# OpAmp_CH1.net
KiCad netlist of a schematic drawn in Altium Designer
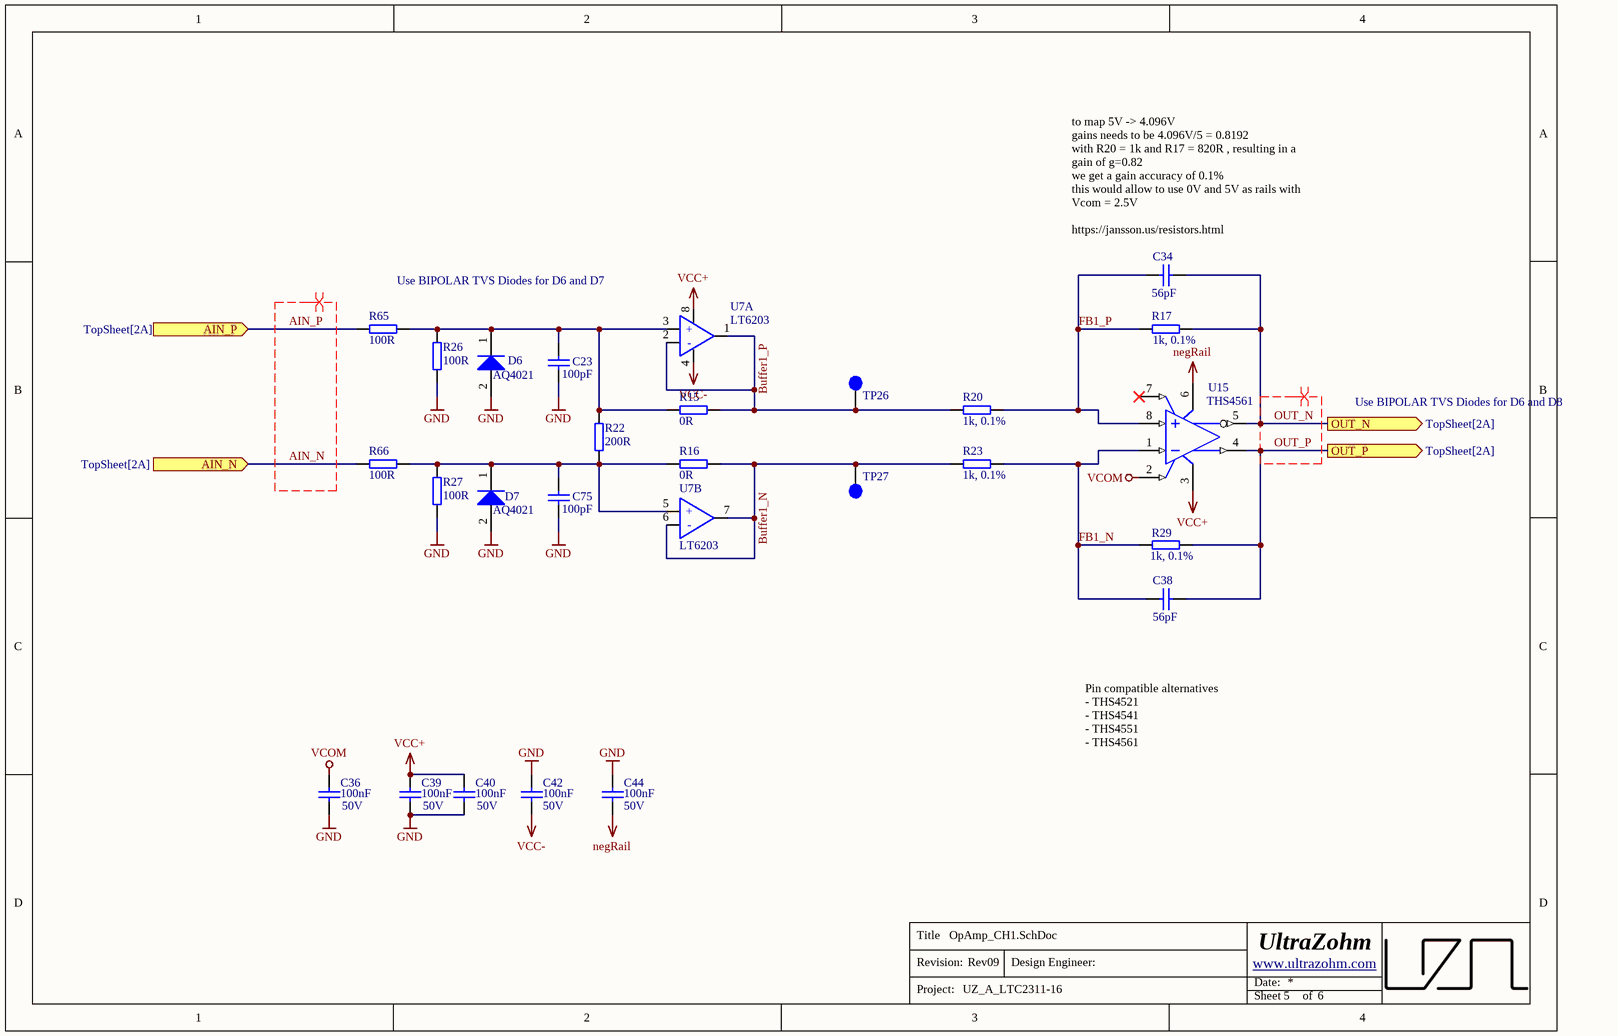
[diagram p0: OpAmp_CH1.SchDoc]

(export (version "E")
  (design (tool "Eeschema 10.0.6"))
  (components
    (comp (ref "C23")
      (value "100pF")
      (footprint "CAPC1608X07N")
      (fields
        (field (name "MF") "Würth Elektronik")
        (field (name "MPN") "885012006057")
        (field (name "VOLTAGE") "50V")
      )
      (libsource (lib "UltraZohm_ADC") (part "Cap_0603"))
    )
    (comp (ref "C34")
      (value "56pF")
      (footprint "CAPC1608X07N")
      (fields
        (field (name "MF") "Kemet")
        (field (name "MPN") "C0603C560J5GACTU")
        (field (name "VOLTAGE") "50V")
      )
      (libsource (lib "UltraZohm_ADC") (part "Cap_0603"))
    )
    (comp (ref "C36")
      (value "100nF")
      (footprint "CAPC1608X07N")
      (fields
        (field (name "MF") "Yageo")
        (field (name "MPN") "CC0603KRX7R9BB104")
        (field (name "VOLTAGE") "50V")
      )
      (libsource (lib "UltraZohm_ADC") (part "Cap_0603"))
    )
    (comp (ref "C38")
      (value "56pF")
      (footprint "CAPC1608X07N")
      (fields
        (field (name "MF") "Kemet")
        (field (name "MPN") "C0603C560J5GACTU")
        (field (name "VOLTAGE") "50V")
      )
      (libsource (lib "UltraZohm_ADC") (part "Cap_0603"))
    )
    (comp (ref "C39")
      (value "100nF")
      (footprint "CAPC1608X07N")
      (fields
        (field (name "MF") "Yageo")
        (field (name "MPN") "CC0603KRX7R9BB104")
        (field (name "VOLTAGE") "50V")
      )
      (libsource (lib "UltraZohm_ADC") (part "Cap_0603"))
    )
    (comp (ref "C40")
      (value "100nF")
      (footprint "CAPC1608X07N")
      (fields
        (field (name "MF") "Yageo")
        (field (name "MPN") "CC0603KRX7R9BB104")
        (field (name "VOLTAGE") "50V")
      )
      (libsource (lib "UltraZohm_ADC") (part "Cap_0603"))
    )
    (comp (ref "C42")
      (value "100nF")
      (footprint "CAPC1608X07N")
      (fields
        (field (name "MF") "Yageo")
        (field (name "MPN") "CC0603KRX7R9BB104")
        (field (name "VOLTAGE") "50V")
      )
      (libsource (lib "UltraZohm_ADC") (part "Cap_0603"))
    )
    (comp (ref "C44")
      (value "100nF")
      (footprint "CAPC1608X07N")
      (fields
        (field (name "MF") "Yageo")
        (field (name "MPN") "CC0603KRX7R9BB104")
        (field (name "VOLTAGE") "50V")
      )
      (libsource (lib "UltraZohm_ADC") (part "Cap_0603"))
    )
    (comp (ref "C75")
      (value "100pF")
      (footprint "CAPC1608X07N")
      (fields
        (field (name "MF") "Würth Elektronik")
        (field (name "MPN") "885012006057")
        (field (name "VOLTAGE") "50V")
      )
      (libsource (lib "UltraZohm_ADC") (part "Cap_0603"))
    )
    (comp (ref "D6")
      (value "AQ4021")
      (footprint "SOD-323_SuppressorDiode")
      (description "ESD Suppressor Diode TVS Bi-Dir 5V")
      (fields (field (name "MF") "Littelfuse") (field (name "MPN") "AQ4021-01FTG-C"))
      (libsource (lib "UltraZohm_ADC") (part "GBLCxx"))
    )
    (comp (ref "D7")
      (value "AQ4021")
      (footprint "SOD-323_SuppressorDiode")
      (description "ESD Suppressor Diode TVS Bi-Dir 5V")
      (fields (field (name "MF") "Littelfuse") (field (name "MPN") "AQ4021-01FTG-C"))
      (libsource (lib "UltraZohm_ADC") (part "GBLCxx"))
    )
    (comp (ref "R15")
      (value "0R")
      (footprint "RESC1608X06N")
      (fields (field (name "MF") "Vishay / Dale") (field (name "MPN") "CRCW06030000Z0EBC"))
      (libsource (lib "UltraZohm_ADC") (part "R_0603"))
    )
    (comp (ref "R16")
      (value "0R")
      (footprint "RESC1608X06N")
      (fields (field (name "MF") "Vishay / Dale") (field (name "MPN") "CRCW06030000Z0EBC"))
      (libsource (lib "UltraZohm_ADC") (part "R_0603"))
    )
    (comp (ref "R17")
      (value "1k, 0.1%")
      (footprint "RESC1608X06N")
      (description "Precision Resistor 1k 0.1% 0603")
      (fields (field (name "MF") "IRC/TT Electronics") (field (name "MPN") "PCF-W0603LF-03-1001-B-P-LT"))
      (libsource (lib "UltraZohm_ADC") (part "R_0603"))
    )
    (comp (ref "R20")
      (value "1k, 0.1%")
      (footprint "RESC1608X06N")
      (description "Precision Resistor 1k 0.1% 0603")
      (fields (field (name "MF") "IRC/TT Electronics") (field (name "MPN") "PCF-W0603LF-03-1001-B-P-LT"))
      (libsource (lib "UltraZohm_ADC") (part "R_0603"))
    )
    (comp (ref "R22")
      (value "200R")
      (footprint "RESC3216X65N")
      (description "WID SMD 1M 5% 0,25W")
      (fields
        (field (name "TOLERANCE") "5%")
        (field (name "MF") "AECOL/Ohmite")
        (field (name "CREATED") "2018_07_20_AGeiger")
      )
      (libsource (lib "UltraZOhm_CarrierBoard") (part "R_1206"))
    )
    (comp (ref "R23")
      (value "1k, 0.1%")
      (footprint "RESC1608X06N")
      (description "Precision Resistor 1k 0.1% 0603")
      (fields (field (name "MF") "IRC/TT Electronics") (field (name "MPN") "PCF-W0603LF-03-1001-B-P-LT"))
      (libsource (lib "UltraZohm_ADC") (part "R_0603"))
    )
    (comp (ref "R26")
      (value "100R")
      (footprint "RESC1608X06N")
      (fields
        (field (name "MF") "Yageo")
        (field (name "MPN") "AC0603FR-13100RL")
        (field (name "TOLERANCE") "1%")
      )
      (libsource (lib "UltraZohm_ADC") (part "R_0603"))
    )
    (comp (ref "R27")
      (value "100R")
      (footprint "RESC1608X06N")
      (fields
        (field (name "MF") "Yageo")
        (field (name "MPN") "AC0603FR-13100RL")
        (field (name "TOLERANCE") "1%")
      )
      (libsource (lib "UltraZohm_ADC") (part "R_0603"))
    )
    (comp (ref "R29")
      (value "1k, 0.1%")
      (footprint "RESC1608X06N")
      (description "Precision Resistor 1k 0.1% 0603")
      (fields (field (name "MF") "IRC/TT Electronics") (field (name "MPN") "PCF-W0603LF-03-1001-B-P-LT"))
      (libsource (lib "UltraZohm_ADC") (part "R_0603"))
    )
    (comp (ref "R65")
      (value "100R")
      (footprint "RESC1608X06N")
      (fields
        (field (name "MF") "Yageo")
        (field (name "MPN") "AC0603FR-13100RL")
        (field (name "TOLERANCE") "1%")
      )
      (libsource (lib "UltraZohm_ADC") (part "R_0603"))
    )
    (comp (ref "R66")
      (value "100R")
      (footprint "RESC1608X06N")
      (fields
        (field (name "MF") "Yageo")
        (field (name "MPN") "AC0603FR-13100RL")
        (field (name "TOLERANCE") "1%")
      )
      (libsource (lib "UltraZohm_ADC") (part "R_0603"))
    )
    (comp (ref "TP26")
      (value "+")
      (footprint "TP_1mm")
      (description "Testpoint 1mm")
      (fields (field (name "CREATED") "2018_06_25_AGeiger"))
      (libsource (lib "UltraZohm_ADC") (part "TP_1mm"))
    )
    (comp (ref "TP27")
      (value "-")
      (footprint "TP_1mm")
      (description "Testpoint 1mm")
      (fields (field (name "CREATED") "2018_06_25_AGeiger"))
      (libsource (lib "UltraZohm_ADC") (part "TP_1mm"))
    )
    (comp (ref "U7")
      (value "LT6203")
      (footprint "MSOP8_3x3-8N")
      (description "2 Ch Low Noise, Low Power OpAmp")
      (fields
        (field (name "MF") "Linear Technology")
        (field (name "MPN") "LT6203CMS8#PBF")
        (field (name "CREATED") "Kreppel_20190830")
      )
      (libsource (lib "UltraZohm_ADC") (part "LT6203_MSOP8"))
    )
    (comp (ref "U15")
      (value "THS4561")
      (footprint "DGK0008A_N")
      (description "IC AMP RRO NEG OUT VLP 8VSSOP (Single Channel fully differential Amplifier)")
      (fields (field (name "MF") "Texas Instruments") (field (name "MPN") "THS4561IDGKR"))
      (libsource (lib "UltraZohm_ADC") (part "THS4521IDGKR"))
    )
  )
  (nets
    (net (code "1") (name "/AIN_N") (class "Default") (node (ref "R66") (pin "1") (pintype "passive")))
    (net (code "2") (name "/AIN_P") (class "Default") (node (ref "R65") (pin "1") (pintype "passive")))
    (net (code "3") (name "/Buffer1_N") (class "Default")
      (node (ref "R16") (pin "2") (pintype "passive"))
      (node (ref "R23") (pin "2") (pintype "passive"))
      (node (ref "TP27") (pin "1") (pintype "passive"))
      (node (ref "U7") (pin "6") (pinfunction "-_6") (pintype "passive"))
      (node (ref "U7") (pin "7") (pintype "passive"))
    )
    (net (code "4") (name "/Buffer1_P") (class "Default")
      (node (ref "R15") (pin "2") (pintype "passive"))
      (node (ref "R20") (pin "1") (pintype "passive"))
      (node (ref "TP26") (pin "1") (pintype "passive"))
      (node (ref "U7") (pin "1") (pintype "passive"))
      (node (ref "U7") (pin "2") (pinfunction "-_2") (pintype "passive"))
    )
    (net (code "5") (name "/FB1_N") (class "Default")
      (node (ref "C38") (pin "1") (pinfunction "1_1") (pintype "passive"))
      (node (ref "R23") (pin "1") (pintype "passive"))
      (node (ref "R29") (pin "1") (pintype "passive"))
      (node (ref "U15") (pin "1") (pinfunction "VIN-_1") (pintype "input"))
    )
    (net (code "6") (name "/FB1_P") (class "Default")
      (node (ref "C34") (pin "1") (pinfunction "1_1") (pintype "passive"))
      (node (ref "R17") (pin "1") (pintype "passive"))
      (node (ref "R20") (pin "2") (pintype "passive"))
      (node (ref "U15") (pin "8") (pinfunction "VIN+_8") (pintype "input"))
    )
    (net (code "7") (name "/OUT_N") (class "Default")
      (node (ref "C34") (pin "2") (pinfunction "2_2") (pintype "passive"))
      (node (ref "R17") (pin "2") (pintype "passive"))
      (node (ref "U15") (pin "5") (pinfunction "VOUT-_5") (pintype "output"))
    )
    (net (code "8") (name "/OUT_P") (class "Default")
      (node (ref "C38") (pin "2") (pinfunction "2_2") (pintype "passive"))
      (node (ref "R29") (pin "2") (pintype "passive"))
      (node (ref "U15") (pin "4") (pinfunction "VOUT+_4") (pintype "output"))
    )
    (net (code "9") (name "GND") (class "Default")
      (node (ref "C23") (pin "2") (pinfunction "2_2") (pintype "passive"))
      (node (ref "C36") (pin "2") (pinfunction "2_2") (pintype "passive"))
      (node (ref "C39") (pin "2") (pinfunction "2_2") (pintype "passive"))
      (node (ref "C40") (pin "2") (pinfunction "2_2") (pintype "passive"))
      (node (ref "C42") (pin "1") (pinfunction "1_1") (pintype "passive"))
      (node (ref "C44") (pin "1") (pinfunction "1_1") (pintype "passive"))
      (node (ref "C75") (pin "2") (pinfunction "2_2") (pintype "passive"))
      (node (ref "D6") (pin "2") (pinfunction "A_2") (pintype "passive"))
      (node (ref "D7") (pin "2") (pinfunction "A_2") (pintype "passive"))
      (node (ref "R26") (pin "1") (pintype "passive"))
      (node (ref "R27") (pin "1") (pintype "passive"))
    )
    (net (code "10") (name "Net-(D6-K)") (class "Default")
      (node (ref "C23") (pin "1") (pinfunction "1_1") (pintype "passive"))
      (node (ref "D6") (pin "1") (pinfunction "K_1") (pintype "passive"))
      (node (ref "R15") (pin "1") (pintype "passive"))
      (node (ref "R22") (pin "2") (pinfunction "2_2") (pintype "passive"))
      (node (ref "R26") (pin "2") (pintype "passive"))
      (node (ref "R65") (pin "2") (pintype "passive"))
      (node (ref "U7") (pin "3") (pinfunction "+_3") (pintype "passive"))
    )
    (net (code "11") (name "Net-(D7-K)") (class "Default")
      (node (ref "C75") (pin "1") (pinfunction "1_1") (pintype "passive"))
      (node (ref "D7") (pin "1") (pinfunction "K_1") (pintype "passive"))
      (node (ref "R16") (pin "1") (pintype "passive"))
      (node (ref "R22") (pin "1") (pinfunction "1_1") (pintype "passive"))
      (node (ref "R27") (pin "2") (pintype "passive"))
      (node (ref "R66") (pin "2") (pintype "passive"))
      (node (ref "U7") (pin "5") (pinfunction "+_5") (pintype "passive"))
    )
    (net (code "12") (name "VCC+") (class "Default")
      (node (ref "C39") (pin "1") (pinfunction "1_1") (pintype "passive"))
      (node (ref "C40") (pin "1") (pinfunction "1_1") (pintype "passive"))
      (node (ref "U15") (pin "3") (pinfunction "VS+_3") (pintype "power_in"))
      (node (ref "U7") (pin "8") (pintype "passive"))
    )
    (net (code "13") (name "VCC-") (class "Default")
      (node (ref "C42") (pin "2") (pinfunction "2_2") (pintype "passive"))
      (node (ref "U7") (pin "4") (pintype "passive"))
    )
    (net (code "14") (name "VCOM") (class "Default")
      (node (ref "C36") (pin "1") (pinfunction "1_1") (pintype "passive"))
      (node (ref "U15") (pin "2") (pinfunction "VOCM_2") (pintype "input"))
    )
    (net (code "15") (name "negRail") (class "Default")
      (node (ref "C44") (pin "2") (pinfunction "2_2") (pintype "passive"))
      (node (ref "U15") (pin "6") (pinfunction "VS-_6") (pintype "power_in"))
    )
    (net (code "16") (name "unconnected-(U15-~{PD}-Pad7)") (class "Default")
      (node (ref "U15") (pin "7") (pinfunction "~{PD}_7") (pintype "input+no_connect"))
    )
  )
)
